# sparkfun-mlx90640-qwiic-breakout.net
KiCad netlist of a schematic drawn in EAGLE
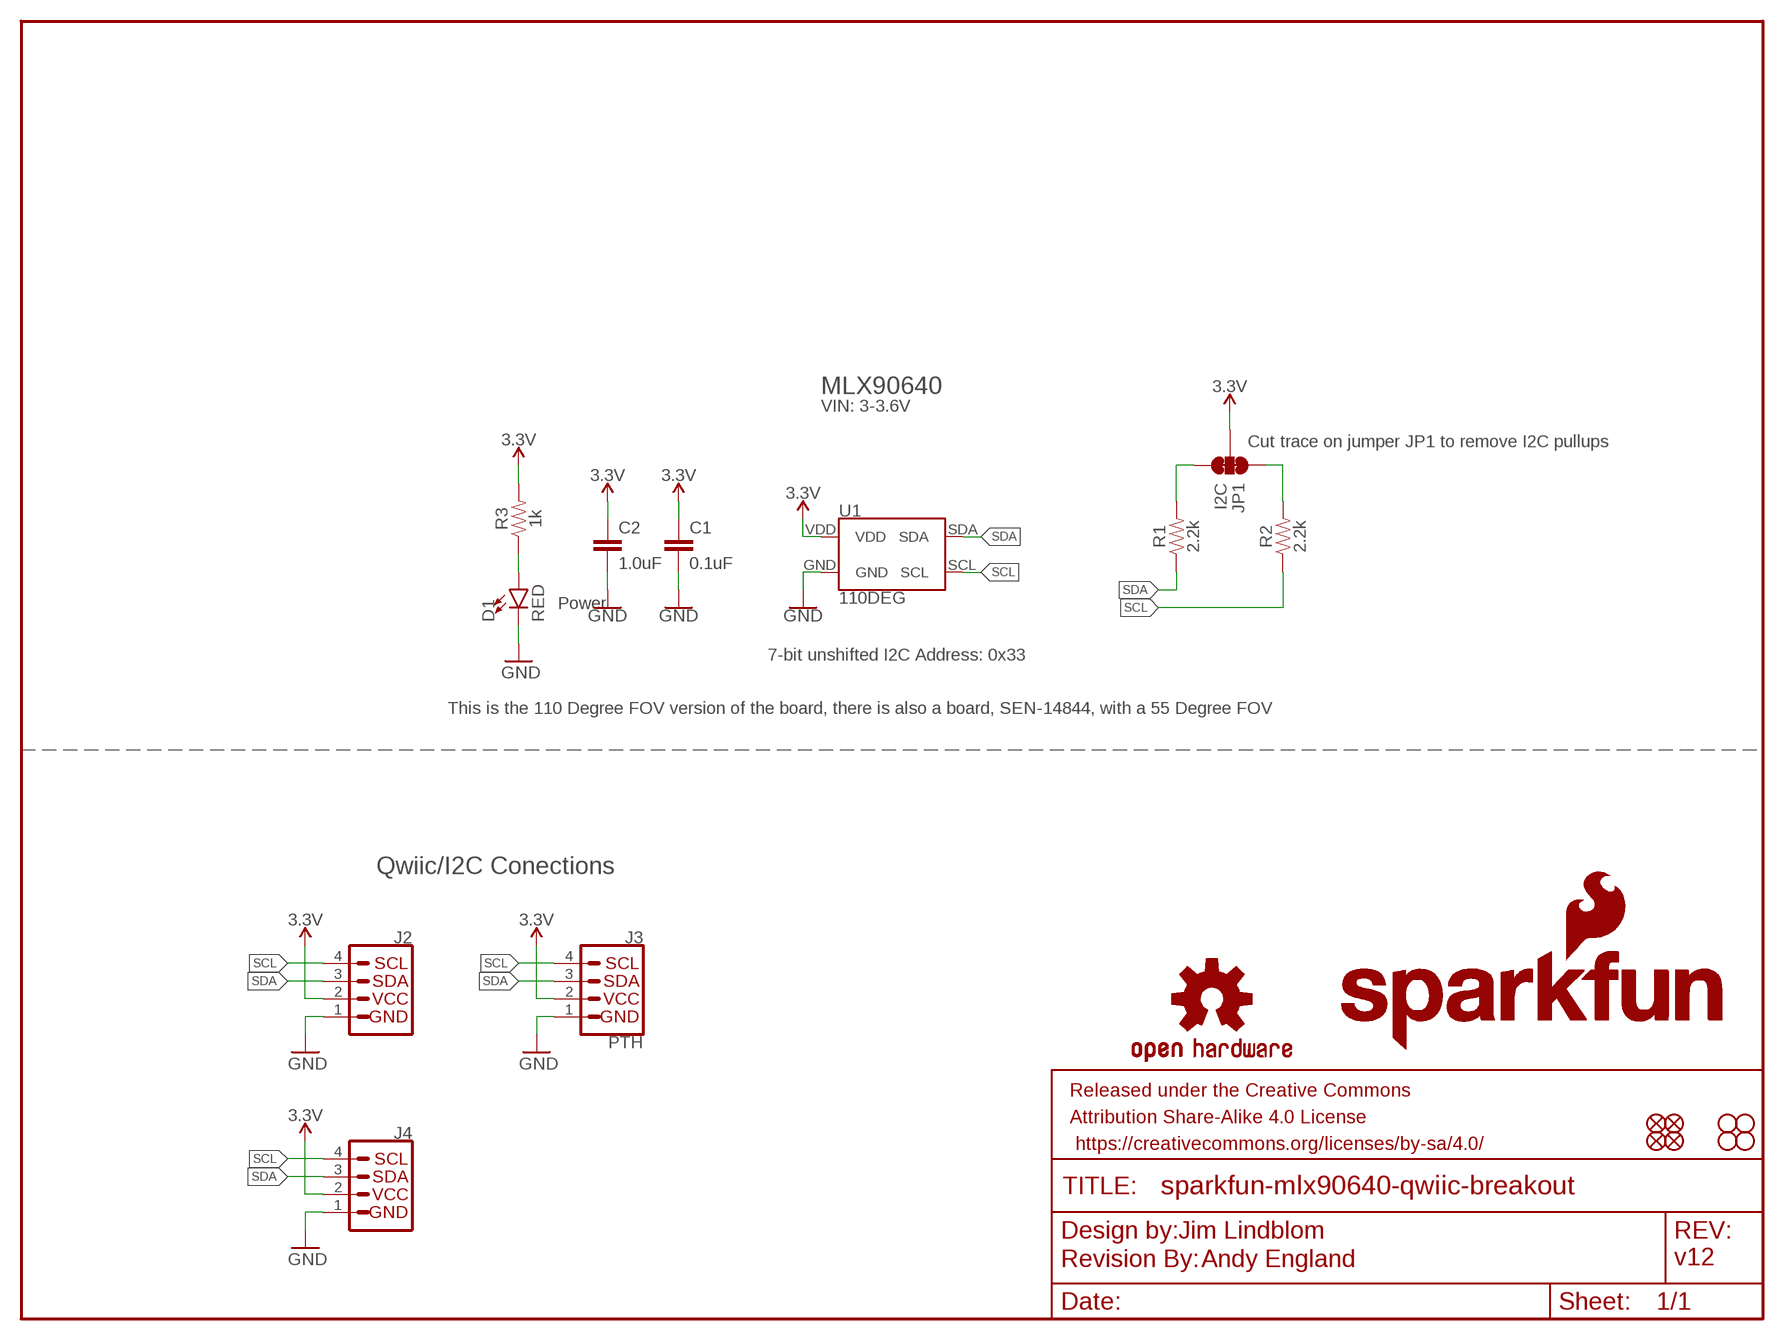
[diagram p0: schematic, sheet 1]

(export (version "E")
  (design (tool "Eeschema 10.0.6"))
  (components
    (comp (ref "C1")
      (value "0.1uF")
      (footprint "eagle-import:0603")
      (libsource (lib "eagle-import") (part "0.1UF-0603-25V-(+80/-20%)"))
    )
    (comp (ref "C2")
      (value "1.0uF")
      (footprint "eagle-import:0603")
      (libsource (lib "eagle-import") (part "1.0UF-0603-16V-10%"))
    )
    (comp (ref "D1")
      (value "RED")
      (footprint "eagle-import:LED-0603")
      (libsource (lib "eagle-import") (part "LED-RED0603"))
    )
    (comp (ref "FRAME1")
      (value "FRAME-LETTER")
      (footprint "eagle-import:CREATIVE_COMMONS")
      (libsource (lib "eagle-import") (part "FRAME-LETTER"))
    )
    (comp (ref "J2")
      (value "QWIIC_CONNECTORJS-1MM")
      (footprint "eagle-import:JST04_1MM_RA")
      (libsource (lib "eagle-import") (part "QWIIC_CONNECTORJS-1MM"))
    )
    (comp (ref "J3")
      (value "PTH")
      (footprint "eagle-import:1X04_NO_SILK")
      (libsource (lib "eagle-import") (part "I2C_STANDARD_NO_SILK"))
    )
    (comp (ref "J4")
      (value "QWIIC_CONNECTORJS-1MM")
      (footprint "eagle-import:JST04_1MM_RA")
      (libsource (lib "eagle-import") (part "QWIIC_CONNECTORJS-1MM"))
    )
    (comp (ref "JP1")
      (value "I2C")
      (footprint "eagle-import:SMT-JUMPER_3_2-NC_TRACE_NO-SILK")
      (libsource (lib "eagle-import") (part "JUMPER-SMT_3_2-NC_TRACE_NO-SILK"))
    )
    (comp (ref "JP2")
      (value "FIDUCIALUFIDUCIAL")
      (footprint "eagle-import:MICRO-FIDUCIAL")
      (libsource (lib "eagle-import") (part "FIDUCIALUFIDUCIAL"))
    )
    (comp (ref "JP3")
      (value "STAND-OFF")
      (footprint "eagle-import:STAND-OFF")
      (libsource (lib "eagle-import") (part "STAND-OFF"))
    )
    (comp (ref "JP4")
      (value "STAND-OFF")
      (footprint "eagle-import:STAND-OFF")
      (libsource (lib "eagle-import") (part "STAND-OFF"))
    )
    (comp (ref "JP5")
      (value "FIDUCIALUFIDUCIAL")
      (footprint "eagle-import:MICRO-FIDUCIAL")
      (libsource (lib "eagle-import") (part "FIDUCIALUFIDUCIAL"))
    )
    (comp (ref "JP6")
      (value "FIDUCIALUFIDUCIAL")
      (footprint "eagle-import:MICRO-FIDUCIAL")
      (libsource (lib "eagle-import") (part "FIDUCIALUFIDUCIAL"))
    )
    (comp (ref "JP7")
      (value "FIDUCIALUFIDUCIAL")
      (footprint "eagle-import:MICRO-FIDUCIAL")
      (libsource (lib "eagle-import") (part "FIDUCIALUFIDUCIAL"))
    )
    (comp (ref "JP8")
      (value "STAND-OFF")
      (footprint "eagle-import:STAND-OFF")
      (libsource (lib "eagle-import") (part "STAND-OFF"))
    )
    (comp (ref "JP9")
      (value "STAND-OFF")
      (footprint "eagle-import:STAND-OFF")
      (libsource (lib "eagle-import") (part "STAND-OFF"))
    )
    (comp (ref "LOGO1")
      (value "OSHW-LOGOMINI")
      (footprint "eagle-import:OSHW-LOGO-MINI")
      (libsource (lib "eagle-import") (part "OSHW-LOGOMINI"))
    )
    (comp (ref "LOGO2")
      (value "SFE_LOGO_NAME_FLAME.1_INCH")
      (footprint "eagle-import:SFE_LOGO_NAME_FLAME_.1")
      (libsource (lib "eagle-import") (part "SFE_LOGO_NAME_FLAME.1_INCH"))
    )
    (comp (ref "LOGO3")
      (value "SFE_LOGO_NAME.1_INCH")
      (footprint "eagle-import:SFE_LOGO_NAME_.1")
      (libsource (lib "eagle-import") (part "SFE_LOGO_NAME.1_INCH"))
    )
    (comp (ref "LOGO4")
      (value "REVISION")
      (footprint "eagle-import:REVISION")
      (libsource (lib "eagle-import") (part "REVISION"))
    )
    (comp (ref "R1")
      (value "2.2k")
      (footprint "eagle-import:0603")
      (libsource (lib "eagle-import") (part "2.2KOHM-0603-1/10W-1%"))
    )
    (comp (ref "R2")
      (value "2.2k")
      (footprint "eagle-import:0603")
      (libsource (lib "eagle-import") (part "2.2KOHM-0603-1/10W-1%"))
    )
    (comp (ref "R3")
      (value "1k")
      (footprint "eagle-import:0603")
      (libsource (lib "eagle-import") (part "1KOHM-0603-1/10W-1%"))
    )
    (comp (ref "U1")
      (value "110DEG")
      (footprint "eagle-import:MLX90540_MLX90640")
      (libsource (lib "eagle-import") (part "MLX90540_MLX906404"))
    )
  )
  (nets
    (net (code "1") (name "3.3V") (class "Default")
      (node (ref "C1") (pin "1") (pinfunction "1_1") (pintype "passive"))
      (node (ref "C2") (pin "1") (pinfunction "1_1") (pintype "passive"))
      (node (ref "J2") (pin "2") (pinfunction "2_2") (pintype "power_in"))
      (node (ref "J3") (pin "2") (pinfunction "VCC_2") (pintype "power_in"))
      (node (ref "J4") (pin "2") (pinfunction "2_2") (pintype "power_in"))
      (node (ref "JP1") (pin "2") (pinfunction "2_2") (pintype "passive"))
      (node (ref "R3") (pin "2") (pinfunction "2_2") (pintype "passive"))
      (node (ref "U1") (pin "VDD") (pinfunction "VDD_VDD") (pintype "bidirectional"))
    )
    (net (code "2") (name "GND") (class "Default")
      (node (ref "C1") (pin "2") (pinfunction "2_2") (pintype "passive"))
      (node (ref "C2") (pin "2") (pinfunction "2_2") (pintype "passive"))
      (node (ref "D1") (pin "C") (pinfunction "C_C") (pintype "passive"))
      (node (ref "J2") (pin "1") (pinfunction "1_1") (pintype "power_in"))
      (node (ref "J3") (pin "1") (pinfunction "GND_1") (pintype "power_in"))
      (node (ref "J4") (pin "1") (pinfunction "1_1") (pintype "power_in"))
      (node (ref "U1") (pin "GND") (pinfunction "GND_GND") (pintype "bidirectional"))
    )
    (net (code "3") (name "Net-(D1-PadA)") (class "Default")
      (node (ref "D1") (pin "A") (pinfunction "A_A") (pintype "passive"))
      (node (ref "R3") (pin "1") (pinfunction "1_1") (pintype "passive"))
    )
    (net (code "4") (name "Net-(JP1-Pad1)") (class "Default")
      (node (ref "JP1") (pin "1") (pinfunction "1_1") (pintype "passive"))
      (node (ref "R2") (pin "2") (pinfunction "2_2") (pintype "passive"))
    )
    (net (code "5") (name "Net-(JP1-Pad3)") (class "Default")
      (node (ref "JP1") (pin "3") (pinfunction "3_3") (pintype "passive"))
      (node (ref "R1") (pin "2") (pinfunction "2_2") (pintype "passive"))
    )
    (net (code "6") (name "SCL") (class "Default")
      (node (ref "J2") (pin "4") (pinfunction "4_4") (pintype "passive"))
      (node (ref "J3") (pin "4") (pinfunction "SCL_4") (pintype "passive"))
      (node (ref "J4") (pin "4") (pinfunction "4_4") (pintype "passive"))
      (node (ref "R2") (pin "1") (pinfunction "1_1") (pintype "passive"))
      (node (ref "U1") (pin "SCL") (pinfunction "SCL_SCL") (pintype "bidirectional"))
    )
    (net (code "7") (name "SDA") (class "Default")
      (node (ref "J2") (pin "3") (pinfunction "3_3") (pintype "passive"))
      (node (ref "J3") (pin "3") (pinfunction "SDA_3") (pintype "passive"))
      (node (ref "J4") (pin "3") (pinfunction "3_3") (pintype "passive"))
      (node (ref "R1") (pin "1") (pinfunction "1_1") (pintype "passive"))
      (node (ref "U1") (pin "SDA") (pinfunction "SDA_SDA") (pintype "bidirectional"))
    )
  )
)
